# chirp-sensor-v2_5_1.net
KiCad netlist of a schematic drawn in EAGLE
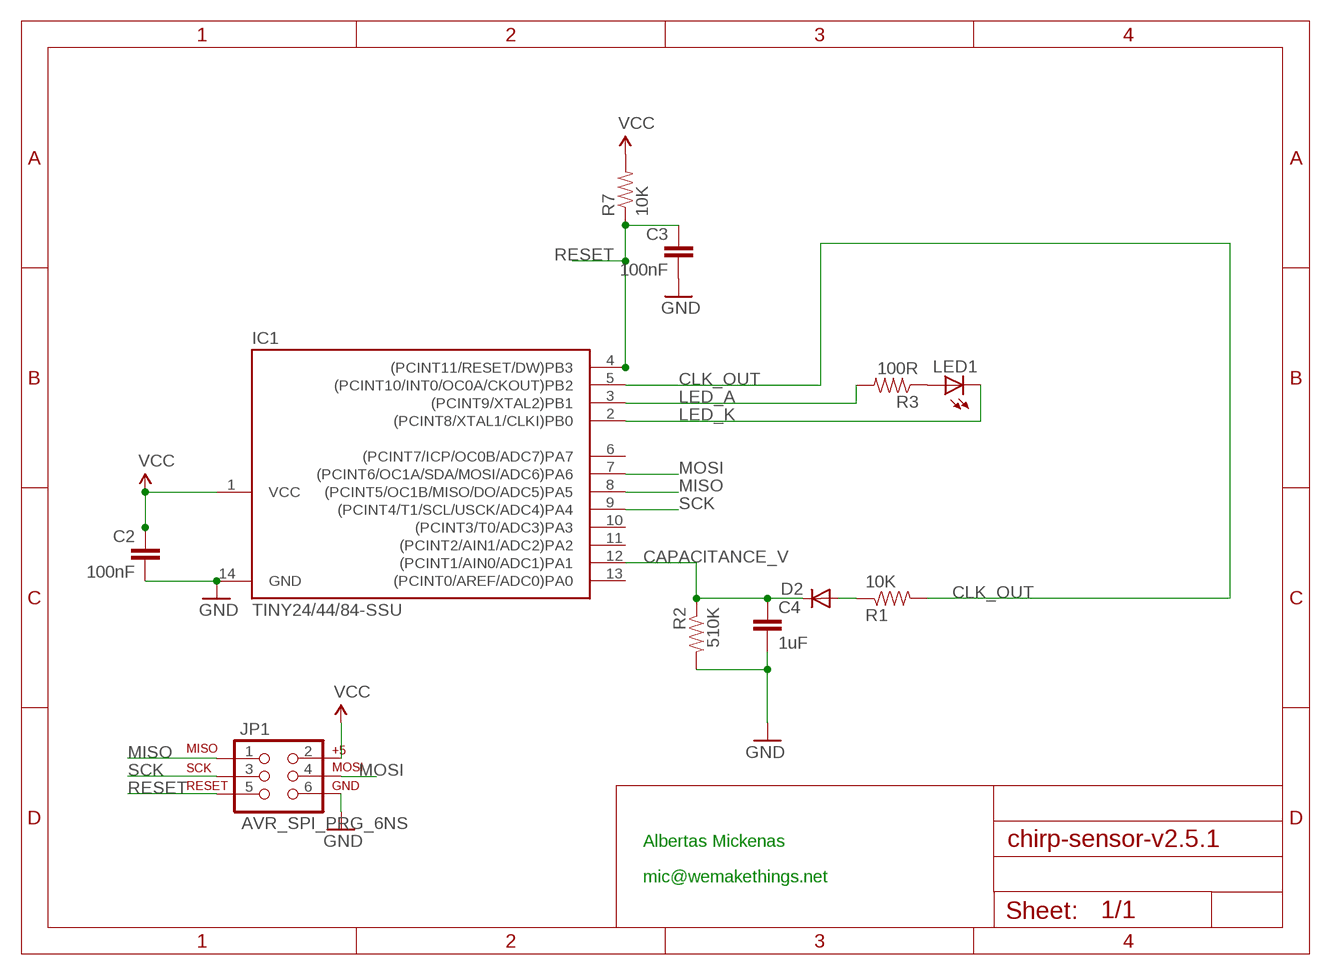
[diagram p0: schematic, sheet 1]

(export (version "E")
  (design (tool "Eeschema 10.0.6"))
  (components
    (comp (ref "C2")
      (value "100nF")
      (footprint "eagle-import:0603-CAP")
      (libsource (lib "eagle-import") (part "CAP0603-CAP"))
    )
    (comp (ref "C3")
      (value "100nF")
      (footprint "eagle-import:0603-CAP")
      (libsource (lib "eagle-import") (part "CAP0603-CAP"))
    )
    (comp (ref "C4")
      (value "1uF")
      (footprint "eagle-import:0603-CAP")
      (libsource (lib "eagle-import") (part "CAP0603-CAP"))
    )
    (comp (ref "D2")
      (value "DIODE-SCHOTTKY_")
      (footprint "eagle-import:SOD-523")
      (libsource (lib "eagle-import") (part "DIODESOD-523"))
    )
    (comp (ref "IC1")
      (value "TINY24/44/84-SSU")
      (footprint "eagle-import:SOIC14")
      (libsource (lib "eagle-import") (part "TINY24/44/84-SSU"))
    )
    (comp (ref "JP1")
      (value "AVR_SPI_PRG_6NS")
      (footprint "eagle-import:2X3-NS")
      (libsource (lib "eagle-import") (part "AVR_SPI_PRG_6NS"))
    )
    (comp (ref "LED1")
      (value "LEDCHIPLED_0805")
      (footprint "eagle-import:CHIPLED_0805")
      (libsource (lib "eagle-import") (part "LEDCHIPLED_0805"))
    )
    (comp (ref "R1")
      (value "10K")
      (footprint "eagle-import:0603-RES")
      (libsource (lib "eagle-import") (part "RESISTOR0603-RES"))
    )
    (comp (ref "R2")
      (value "510K")
      (footprint "eagle-import:0603-RES")
      (libsource (lib "eagle-import") (part "RESISTOR0603-RES"))
    )
    (comp (ref "R3")
      (value "100R")
      (footprint "eagle-import:0603-RES")
      (libsource (lib "eagle-import") (part "RESISTOR0603-RES"))
    )
    (comp (ref "R7")
      (value "10K")
      (footprint "eagle-import:0603-RES")
      (libsource (lib "eagle-import") (part "RESISTOR0603-RES"))
    )
  )
  (nets
    (net (code "1") (name "/CAPACITANCE_V") (class "Default")
      (node (ref "C4") (pin "1") (pinfunction "1_1") (pintype "passive"))
      (node (ref "D2") (pin "K") (pinfunction "C_K") (pintype "passive"))
      (node (ref "IC1") (pin "12") (pinfunction "(PCINT1/AIN0/ADC1)PA1_12") (pintype "bidirectional"))
      (node (ref "R2") (pin "1") (pinfunction "1_1") (pintype "passive"))
    )
    (net (code "2") (name "/CLK_OUT") (class "Default")
      (node (ref "IC1") (pin "5") (pinfunction "(PCINT10/INT0/OC0A/CKOUT)PB2_5") (pintype "bidirectional"))
      (node (ref "R1") (pin "2") (pinfunction "2_2") (pintype "passive"))
    )
    (net (code "3") (name "/LED_A") (class "Default")
      (node (ref "IC1") (pin "3") (pinfunction "(PCINT9/XTAL2)PB1_3") (pintype "bidirectional"))
      (node (ref "R3") (pin "2") (pinfunction "2_2") (pintype "passive"))
    )
    (net (code "4") (name "/LED_K") (class "Default")
      (node (ref "IC1") (pin "2") (pinfunction "(PCINT8/XTAL1/CLKI)PB0_2") (pintype "bidirectional"))
      (node (ref "LED1") (pin "C") (pinfunction "C_C") (pintype "passive"))
    )
    (net (code "5") (name "/MISO") (class "Default")
      (node (ref "IC1") (pin "8") (pinfunction "(PCINT5/OC1B/MISO/DO/ADC5)PA5_8") (pintype "bidirectional"))
      (node (ref "JP1") (pin "1") (pinfunction "1_1") (pintype "passive"))
    )
    (net (code "6") (name "/MOSI") (class "Default")
      (node (ref "IC1") (pin "7") (pinfunction "(PCINT6/OC1A/SDA/MOSI/ADC6)PA6_7") (pintype "bidirectional"))
      (node (ref "JP1") (pin "4") (pinfunction "4_4") (pintype "passive"))
    )
    (net (code "7") (name "/RESET") (class "Default")
      (node (ref "C3") (pin "1") (pinfunction "1_1") (pintype "passive"))
      (node (ref "IC1") (pin "4") (pinfunction "(PCINT11/RESET/DW)PB3_4") (pintype "bidirectional"))
      (node (ref "JP1") (pin "5") (pinfunction "5_5") (pintype "passive"))
      (node (ref "R7") (pin "1") (pinfunction "1_1") (pintype "passive"))
    )
    (net (code "8") (name "/SCK") (class "Default")
      (node (ref "IC1") (pin "9") (pinfunction "(PCINT4/T1/SCL/USCK/ADC4)PA4_9") (pintype "bidirectional"))
      (node (ref "JP1") (pin "3") (pinfunction "3_3") (pintype "passive"))
    )
    (net (code "9") (name "GND") (class "Default")
      (node (ref "C2") (pin "2") (pinfunction "2_2") (pintype "passive"))
      (node (ref "C3") (pin "2") (pinfunction "2_2") (pintype "passive"))
      (node (ref "C4") (pin "2") (pinfunction "2_2") (pintype "passive"))
      (node (ref "IC1") (pin "14") (pinfunction "GND_14") (pintype "power_in"))
      (node (ref "JP1") (pin "6") (pinfunction "6_6") (pintype "passive"))
      (node (ref "R2") (pin "2") (pinfunction "2_2") (pintype "passive"))
    )
    (net (code "10") (name "Net-(D2-PadA)") (class "Default")
      (node (ref "D2") (pin "A") (pinfunction "A_A") (pintype "passive"))
      (node (ref "R1") (pin "1") (pinfunction "1_1") (pintype "passive"))
    )
    (net (code "11") (name "Net-(LED1-PadA)") (class "Default")
      (node (ref "LED1") (pin "A") (pinfunction "A_A") (pintype "passive"))
      (node (ref "R3") (pin "1") (pinfunction "1_1") (pintype "passive"))
    )
    (net (code "12") (name "VCC") (class "Default")
      (node (ref "C2") (pin "1") (pinfunction "1_1") (pintype "passive"))
      (node (ref "IC1") (pin "1") (pinfunction "VCC_1") (pintype "power_in"))
      (node (ref "JP1") (pin "2") (pinfunction "2_2") (pintype "passive"))
      (node (ref "R7") (pin "2") (pinfunction "2_2") (pintype "passive"))
    )
    (net (code "13") (name "unconnected-(IC1-(PCINT0{slash}AREF{slash}ADC0)PA0-Pad13)") (class "Default")
      (node (ref "IC1") (pin "13") (pinfunction "(PCINT0/AREF/ADC0)PA0_13") (pintype "bidirectional"))
    )
    (net (code "14") (name "unconnected-(IC1-(PCINT2{slash}AIN1{slash}ADC2)PA2-Pad11)") (class "Default")
      (node (ref "IC1") (pin "11") (pinfunction "(PCINT2/AIN1/ADC2)PA2_11") (pintype "bidirectional"))
    )
    (net (code "15") (name "unconnected-(IC1-(PCINT3{slash}T0{slash}ADC3)PA3-Pad10)") (class "Default")
      (node (ref "IC1") (pin "10") (pinfunction "(PCINT3/T0/ADC3)PA3_10") (pintype "bidirectional"))
    )
    (net (code "16") (name "unconnected-(IC1-(PCINT7{slash}ICP{slash}OC0B{slash}ADC7)PA7-Pad6)") (class "Default")
      (node (ref "IC1") (pin "6") (pinfunction "(PCINT7/ICP/OC0B/ADC7)PA7_6") (pintype "bidirectional"))
    )
  )
)
